# quadrature_generator.net
KiCad netlist of a schematic drawn in EAGLE
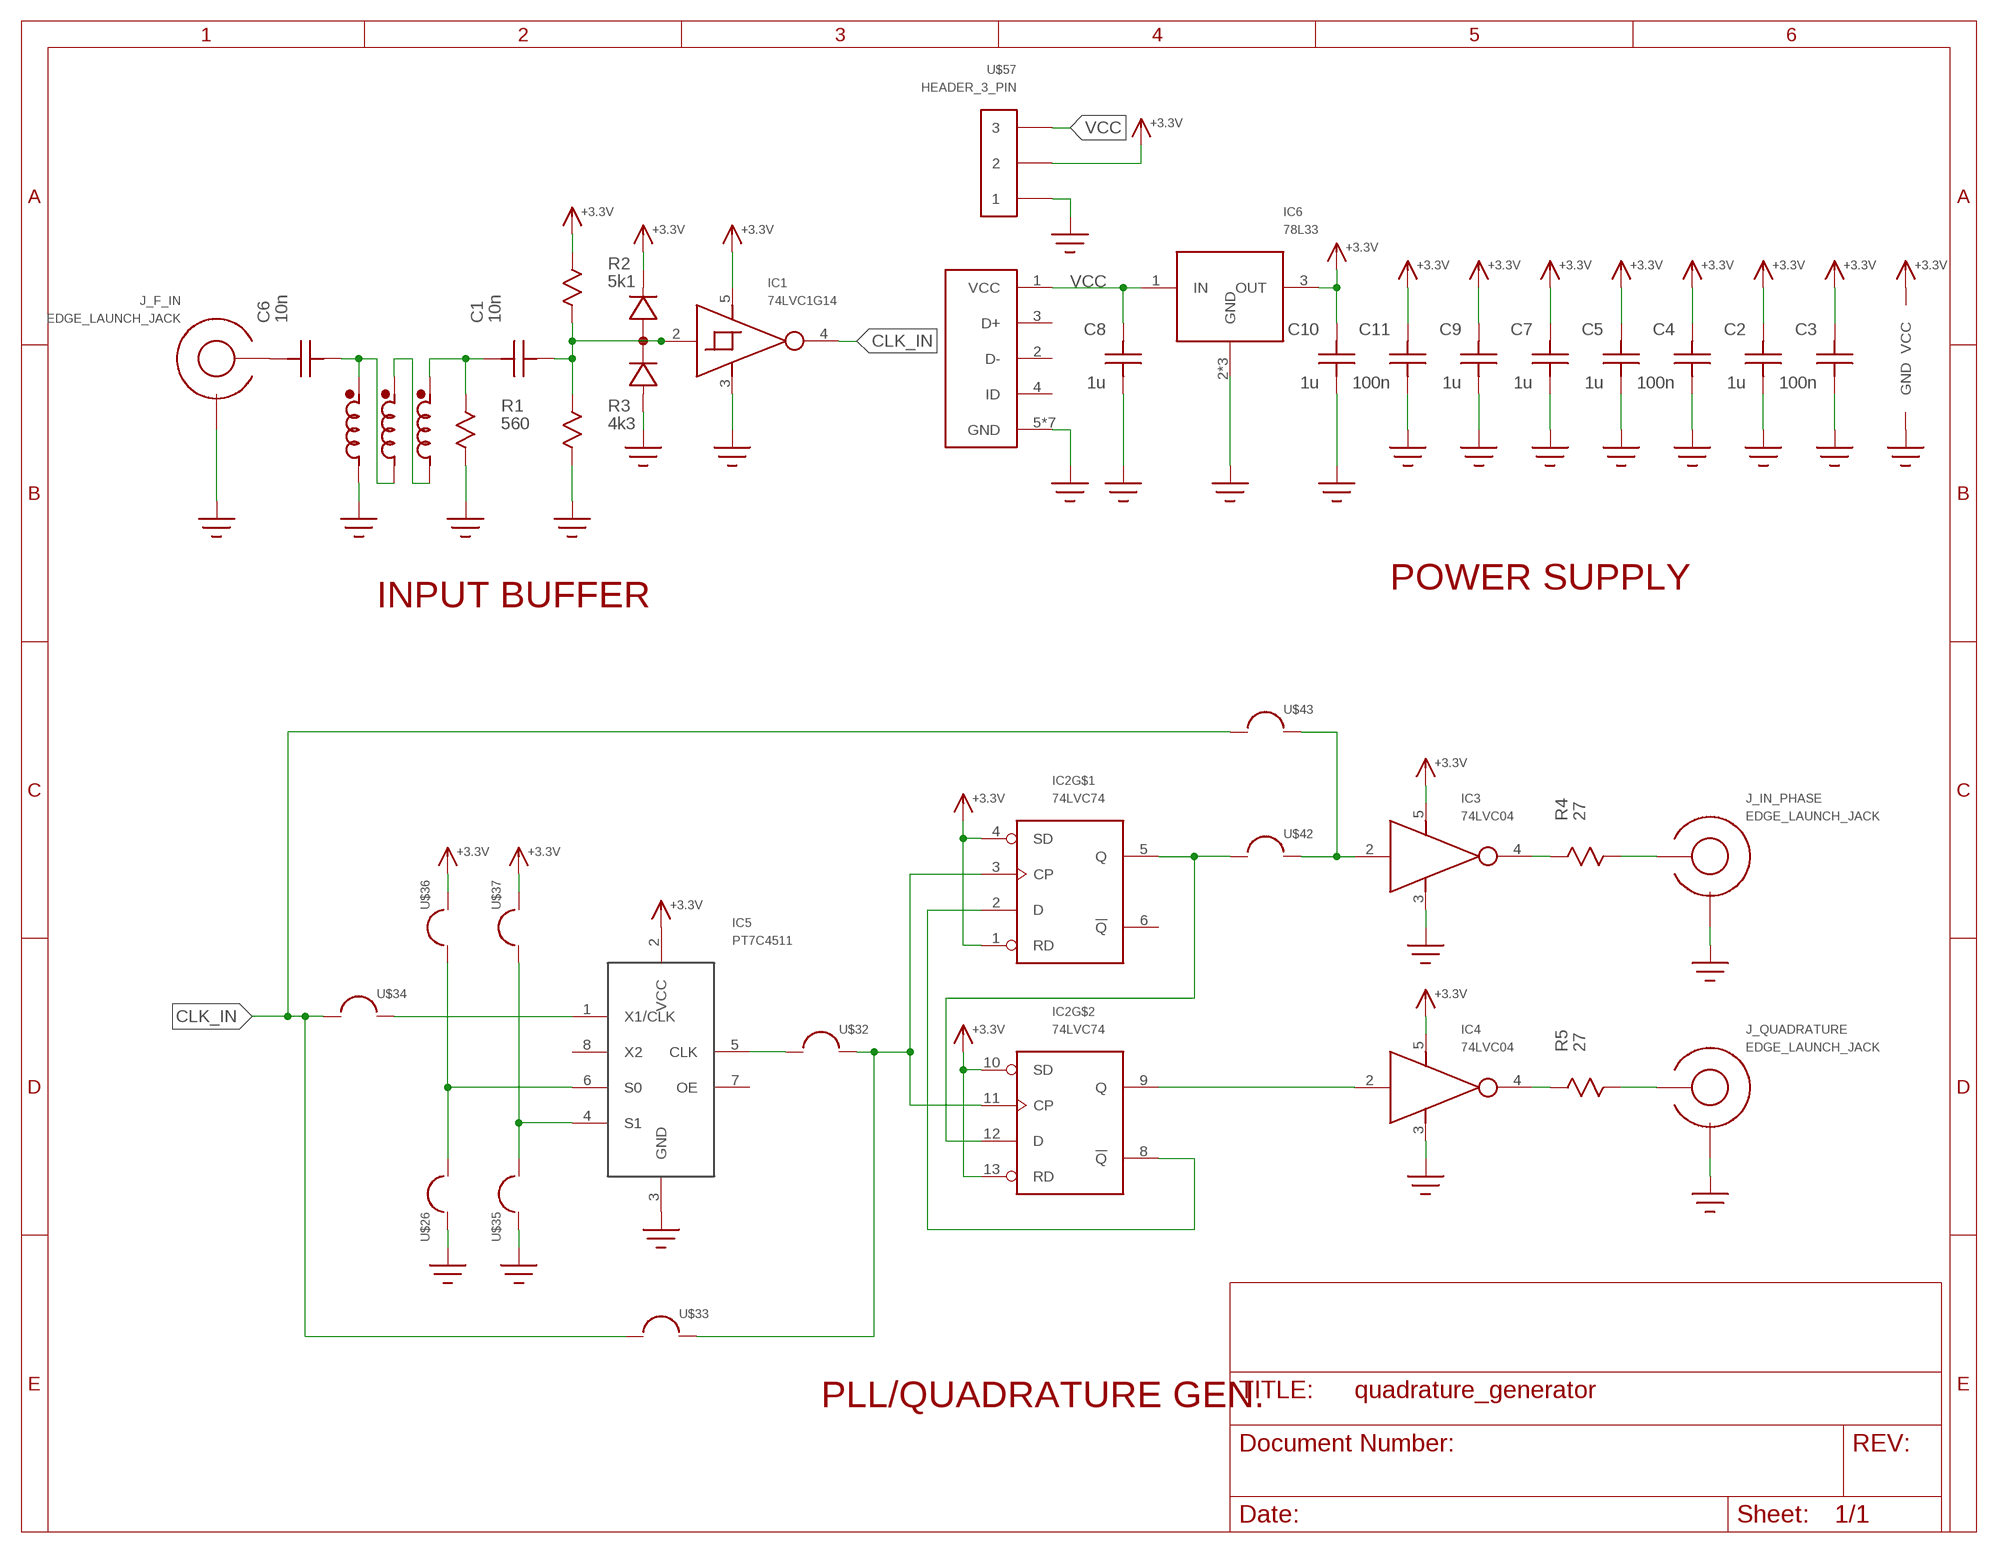
[diagram p0: schematic, sheet 1]

(export (version "E")
  (design (tool "Eeschema 10.0.6"))
  (components
    (comp (ref "C1")
      (value "10n")
      (footprint "eagle-import:0805")
      (libsource (lib "eagle-import") (part "C0805"))
    )
    (comp (ref "C2")
      (value "1u")
      (footprint "eagle-import:0805")
      (libsource (lib "eagle-import") (part "C0805"))
    )
    (comp (ref "C3")
      (value "100n")
      (footprint "eagle-import:0805")
      (libsource (lib "eagle-import") (part "C0805"))
    )
    (comp (ref "C4")
      (value "100n")
      (footprint "eagle-import:0805")
      (libsource (lib "eagle-import") (part "C0805"))
    )
    (comp (ref "C5")
      (value "1u")
      (footprint "eagle-import:0805")
      (libsource (lib "eagle-import") (part "C0805"))
    )
    (comp (ref "C6")
      (value "10n")
      (footprint "eagle-import:0805")
      (libsource (lib "eagle-import") (part "C0805"))
    )
    (comp (ref "C7")
      (value "1u")
      (footprint "eagle-import:0805")
      (libsource (lib "eagle-import") (part "C0805"))
    )
    (comp (ref "C8")
      (value "1u")
      (footprint "eagle-import:0805")
      (libsource (lib "eagle-import") (part "C0805"))
    )
    (comp (ref "C9")
      (value "1u")
      (footprint "eagle-import:0805")
      (libsource (lib "eagle-import") (part "C0805"))
    )
    (comp (ref "C10")
      (value "1u")
      (footprint "eagle-import:0805")
      (libsource (lib "eagle-import") (part "C0805"))
    )
    (comp (ref "C11")
      (value "100n")
      (footprint "eagle-import:0805")
      (libsource (lib "eagle-import") (part "C0805"))
    )
    (comp (ref "IC1")
      (value "74LVC1G14")
      (footprint "eagle-import:SOT23-5")
      (libsource (lib "eagle-import") (part "74LVC1G14"))
    )
    (comp (ref "IC2")
      (value "74LVC74")
      (footprint "eagle-import:SOIC14_NARROW")
      (libsource (lib "eagle-import") (part "74LVC74"))
    )
    (comp (ref "IC3")
      (value "74LVC04")
      (footprint "eagle-import:SOT23-5")
      (libsource (lib "eagle-import") (part "74LVC04"))
    )
    (comp (ref "IC4")
      (value "74LVC04")
      (footprint "eagle-import:SOT23-5")
      (libsource (lib "eagle-import") (part "74LVC04"))
    )
    (comp (ref "IC5")
      (value "PT7C4511")
      (footprint "eagle-import:SOIC8")
      (libsource (lib "eagle-import") (part "PT7C4511"))
    )
    (comp (ref "IC6")
      (value "78L33")
      (footprint "eagle-import:SOT-89")
      (libsource (lib "eagle-import") (part "REGULATOR_3TERM"))
    )
    (comp (ref "J_F_IN")
      (value "EDGE_LAUNCH_JACK")
      (footprint "eagle-import:EDGE_LAUNCH_RF_CON")
      (libsource (lib "eagle-import") (part "EDGE_LAUNCH_JACK"))
    )
    (comp (ref "J_IN_PHASE")
      (value "EDGE_LAUNCH_JACK")
      (footprint "eagle-import:EDGE_LAUNCH_RF_CON")
      (libsource (lib "eagle-import") (part "EDGE_LAUNCH_JACK"))
    )
    (comp (ref "J_QUADRATURE")
      (value "EDGE_LAUNCH_JACK")
      (footprint "eagle-import:EDGE_LAUNCH_RF_CON")
      (libsource (lib "eagle-import") (part "EDGE_LAUNCH_JACK"))
    )
    (comp (ref "R1")
      (value "560")
      (footprint "eagle-import:R1206")
      (libsource (lib "eagle-import") (part "R1206"))
    )
    (comp (ref "R2")
      (value "5k1")
      (footprint "eagle-import:R0805")
      (libsource (lib "eagle-import") (part "R0805"))
    )
    (comp (ref "R3")
      (value "4k3")
      (footprint "eagle-import:R0805")
      (libsource (lib "eagle-import") (part "R0805"))
    )
    (comp (ref "R4")
      (value "27")
      (footprint "eagle-import:R1206")
      (libsource (lib "eagle-import") (part "R1206"))
    )
    (comp (ref "R5")
      (value "27")
      (footprint "eagle-import:R1206")
      (libsource (lib "eagle-import") (part "R1206"))
    )
    (comp (ref "U$1")
      (value "FT37_TRIFILAR_1")
      (footprint "eagle-import:FT37_TRIFILAR_VERT_NC")
      (libsource (lib "eagle-import") (part "FT37_TRIFILAR_1"))
    )
    (comp (ref "U$18")
      (value "USB_JACK")
      (footprint "eagle-import:FCI_MICRO_USB")
      (libsource (lib "eagle-import") (part "USB_JACK"))
    )
    (comp (ref "U$26")
      (value "SOLDER_BRIDGE")
      (footprint "eagle-import:SOLDER_BRIDGE")
      (libsource (lib "eagle-import") (part "SOLDER_BRIDGE"))
    )
    (comp (ref "U$32")
      (value "SOLDER_BRIDGE")
      (footprint "eagle-import:SOLDER_BRIDGE")
      (libsource (lib "eagle-import") (part "SOLDER_BRIDGE"))
    )
    (comp (ref "U$33")
      (value "SOLDER_BRIDGE")
      (footprint "eagle-import:SOLDER_BRIDGE")
      (libsource (lib "eagle-import") (part "SOLDER_BRIDGE"))
    )
    (comp (ref "U$34")
      (value "SOLDER_BRIDGE")
      (footprint "eagle-import:SOLDER_BRIDGE")
      (libsource (lib "eagle-import") (part "SOLDER_BRIDGE"))
    )
    (comp (ref "U$35")
      (value "SOLDER_BRIDGE")
      (footprint "eagle-import:SOLDER_BRIDGE")
      (libsource (lib "eagle-import") (part "SOLDER_BRIDGE"))
    )
    (comp (ref "U$36")
      (value "SOLDER_BRIDGE")
      (footprint "eagle-import:SOLDER_BRIDGE")
      (libsource (lib "eagle-import") (part "SOLDER_BRIDGE"))
    )
    (comp (ref "U$37")
      (value "SOLDER_BRIDGE")
      (footprint "eagle-import:SOLDER_BRIDGE")
      (libsource (lib "eagle-import") (part "SOLDER_BRIDGE"))
    )
    (comp (ref "U$42")
      (value "SOLDER_BRIDGE")
      (footprint "eagle-import:SOLDER_BRIDGE")
      (libsource (lib "eagle-import") (part "SOLDER_BRIDGE"))
    )
    (comp (ref "U$43")
      (value "SOLDER_BRIDGE")
      (footprint "eagle-import:SOLDER_BRIDGE")
      (libsource (lib "eagle-import") (part "SOLDER_BRIDGE"))
    )
    (comp (ref "U$50")
      (value "MMBD7000L")
      (footprint "eagle-import:SOT-23")
      (libsource (lib "eagle-import") (part "MMBD7000L"))
    )
    (comp (ref "U$57")
      (value "HEADER_3_PIN")
      (footprint "eagle-import:HEADER_3_PIN")
      (libsource (lib "eagle-import") (part "HEADER_3_PIN"))
    )
  )
  (nets
    (net (code "1") (name "+3.3V") (class "Default")
      (node (ref "C10") (pin "P$1") (pinfunction "P$1_P$1") (pintype "bidirectional"))
      (node (ref "C11") (pin "P$1") (pinfunction "P$1_P$1") (pintype "bidirectional"))
      (node (ref "C2") (pin "P$1") (pinfunction "P$1_P$1") (pintype "bidirectional"))
      (node (ref "C3") (pin "P$1") (pinfunction "P$1_P$1") (pintype "bidirectional"))
      (node (ref "C4") (pin "P$1") (pinfunction "P$1_P$1") (pintype "bidirectional"))
      (node (ref "C5") (pin "P$1") (pinfunction "P$1_P$1") (pintype "bidirectional"))
      (node (ref "C7") (pin "P$1") (pinfunction "P$1_P$1") (pintype "bidirectional"))
      (node (ref "C9") (pin "P$1") (pinfunction "P$1_P$1") (pintype "bidirectional"))
      (node (ref "IC1") (pin "5") (pinfunction "VCC_5") (pintype "bidirectional"))
      (node (ref "IC2") (pin "1") (pinfunction "RD_1") (pintype "bidirectional"))
      (node (ref "IC2") (pin "10") (pinfunction "SD_10") (pintype "bidirectional"))
      (node (ref "IC2") (pin "13") (pinfunction "RD_13") (pintype "bidirectional"))
      (node (ref "IC2") (pin "14") (pinfunction "VCC_14") (pintype "bidirectional"))
      (node (ref "IC2") (pin "4") (pinfunction "SD_4") (pintype "bidirectional"))
      (node (ref "IC3") (pin "5") (pinfunction "VCC_5") (pintype "bidirectional"))
      (node (ref "IC4") (pin "5") (pinfunction "VCC_5") (pintype "bidirectional"))
      (node (ref "IC5") (pin "2") (pinfunction "VCC_2") (pintype "bidirectional"))
      (node (ref "IC6") (pin "3") (pinfunction "OUT_3") (pintype "bidirectional"))
      (node (ref "R2") (pin "P$1") (pinfunction "P$3_P$1") (pintype "bidirectional"))
      (node (ref "U$36") (pin "2@1") (pinfunction "P$2_2@1") (pintype "bidirectional"))
      (node (ref "U$36") (pin "2@2") (pinfunction "P$2_2@2") (pintype "bidirectional"))
      (node (ref "U$36") (pin "2@3") (pinfunction "P$2_2@3") (pintype "bidirectional"))
      (node (ref "U$37") (pin "2@1") (pinfunction "P$2_2@1") (pintype "bidirectional"))
      (node (ref "U$37") (pin "2@2") (pinfunction "P$2_2@2") (pintype "bidirectional"))
      (node (ref "U$37") (pin "2@3") (pinfunction "P$2_2@3") (pintype "bidirectional"))
      (node (ref "U$50") (pin "2") (pinfunction "CATHODE_2") (pintype "bidirectional"))
      (node (ref "U$57") (pin "2") (pinfunction "2_2") (pintype "bidirectional"))
    )
    (net (code "2") (name "CLK_IN") (class "Default")
      (node (ref "IC1") (pin "4") (pinfunction "OUT_4") (pintype "bidirectional"))
      (node (ref "U$33") (pin "1") (pinfunction "P$1_1") (pintype "bidirectional"))
      (node (ref "U$34") (pin "1") (pinfunction "P$1_1") (pintype "bidirectional"))
      (node (ref "U$43") (pin "1") (pinfunction "P$1_1") (pintype "bidirectional"))
    )
    (net (code "3") (name "GND") (class "Default")
      (node (ref "C10") (pin "P$2") (pinfunction "P$2_P$2") (pintype "bidirectional"))
      (node (ref "C11") (pin "P$2") (pinfunction "P$2_P$2") (pintype "bidirectional"))
      (node (ref "C2") (pin "P$2") (pinfunction "P$2_P$2") (pintype "bidirectional"))
      (node (ref "C3") (pin "P$2") (pinfunction "P$2_P$2") (pintype "bidirectional"))
      (node (ref "C4") (pin "P$2") (pinfunction "P$2_P$2") (pintype "bidirectional"))
      (node (ref "C5") (pin "P$2") (pinfunction "P$2_P$2") (pintype "bidirectional"))
      (node (ref "C7") (pin "P$2") (pinfunction "P$2_P$2") (pintype "bidirectional"))
      (node (ref "C8") (pin "P$2") (pinfunction "P$2_P$2") (pintype "bidirectional"))
      (node (ref "C9") (pin "P$2") (pinfunction "P$2_P$2") (pintype "bidirectional"))
      (node (ref "IC1") (pin "3") (pinfunction "GND_3") (pintype "bidirectional"))
      (node (ref "IC2") (pin "7") (pinfunction "GND_7") (pintype "bidirectional"))
      (node (ref "IC3") (pin "3") (pinfunction "GND_3") (pintype "bidirectional"))
      (node (ref "IC4") (pin "3") (pinfunction "GND_3") (pintype "bidirectional"))
      (node (ref "IC5") (pin "3") (pinfunction "GND_3") (pintype "bidirectional"))
      (node (ref "IC6") (pin "2") (pinfunction "GND_2") (pintype "bidirectional"))
      (node (ref "IC6") (pin "TAB") (pinfunction "GND_TAB") (pintype "bidirectional"))
      (node (ref "IC6") (pin "TAB@1") (pinfunction "GND_TAB@1") (pintype "bidirectional"))
      (node (ref "J_F_IN") (pin "GND@1") (pinfunction "GND_GND@1") (pintype "bidirectional"))
      (node (ref "J_F_IN") (pin "GND@2") (pinfunction "GND_GND@2") (pintype "bidirectional"))
      (node (ref "J_IN_PHASE") (pin "GND@1") (pinfunction "GND_GND@1") (pintype "bidirectional"))
      (node (ref "J_IN_PHASE") (pin "GND@2") (pinfunction "GND_GND@2") (pintype "bidirectional"))
      (node (ref "J_QUADRATURE") (pin "GND@1") (pinfunction "GND_GND@1") (pintype "bidirectional"))
      (node (ref "J_QUADRATURE") (pin "GND@2") (pinfunction "GND_GND@2") (pintype "bidirectional"))
      (node (ref "R1") (pin "P$2") (pinfunction "P$4_P$2") (pintype "bidirectional"))
      (node (ref "R3") (pin "P$2") (pinfunction "P$4_P$2") (pintype "bidirectional"))
      (node (ref "U$1") (pin "P$R1") (pinfunction "R1_P$R1") (pintype "bidirectional"))
      (node (ref "U$18") (pin "5") (pinfunction "GND_5") (pintype "bidirectional"))
      (node (ref "U$18") (pin "GND1") (pinfunction "GND_GND1") (pintype "bidirectional"))
      (node (ref "U$18") (pin "GND2") (pinfunction "GND_GND2") (pintype "bidirectional"))
      (node (ref "U$18") (pin "GND3") (pinfunction "GND_GND3") (pintype "bidirectional"))
      (node (ref "U$18") (pin "GND4") (pinfunction "GND_GND4") (pintype "bidirectional"))
      (node (ref "U$18") (pin "GND5") (pinfunction "GND_GND5") (pintype "bidirectional"))
      (node (ref "U$18") (pin "GND6") (pinfunction "GND_GND6") (pintype "bidirectional"))
      (node (ref "U$26") (pin "2@1") (pinfunction "P$2_2@1") (pintype "bidirectional"))
      (node (ref "U$26") (pin "2@2") (pinfunction "P$2_2@2") (pintype "bidirectional"))
      (node (ref "U$26") (pin "2@3") (pinfunction "P$2_2@3") (pintype "bidirectional"))
      (node (ref "U$35") (pin "2@1") (pinfunction "P$2_2@1") (pintype "bidirectional"))
      (node (ref "U$35") (pin "2@2") (pinfunction "P$2_2@2") (pintype "bidirectional"))
      (node (ref "U$35") (pin "2@3") (pinfunction "P$2_2@3") (pintype "bidirectional"))
      (node (ref "U$50") (pin "1") (pinfunction "ANODE_1") (pintype "bidirectional"))
      (node (ref "U$57") (pin "1") (pinfunction "1_1") (pintype "bidirectional"))
    )
    (net (code "4") (name "Net-(C6-PadP$2)") (class "Default")
      (node (ref "C6") (pin "P$2") (pinfunction "P$2_P$2") (pintype "bidirectional"))
      (node (ref "J_F_IN") (pin "SIG") (pinfunction "SIG_SIG") (pintype "bidirectional"))
    )
    (net (code "5") (name "Net-(IC1-IN)") (class "Default")
      (node (ref "C1") (pin "P$1") (pinfunction "P$1_P$1") (pintype "bidirectional"))
      (node (ref "IC1") (pin "2") (pinfunction "IN_2") (pintype "bidirectional"))
      (node (ref "R2") (pin "P$2") (pinfunction "P$4_P$2") (pintype "bidirectional"))
      (node (ref "R3") (pin "P$1") (pinfunction "P$3_P$1") (pintype "bidirectional"))
      (node (ref "U$50") (pin "3") (pinfunction "COMMON_3") (pintype "bidirectional"))
    )
    (net (code "6") (name "Net-(IC2A-CP)") (class "Default")
      (node (ref "IC2") (pin "11") (pinfunction "CP_11") (pintype "bidirectional"))
      (node (ref "IC2") (pin "3") (pinfunction "CP_3") (pintype "bidirectional"))
      (node (ref "U$32") (pin "2@1") (pinfunction "P$2_2@1") (pintype "bidirectional"))
      (node (ref "U$32") (pin "2@2") (pinfunction "P$2_2@2") (pintype "bidirectional"))
      (node (ref "U$32") (pin "2@3") (pinfunction "P$2_2@3") (pintype "bidirectional"))
      (node (ref "U$33") (pin "2@1") (pinfunction "P$2_2@1") (pintype "bidirectional"))
      (node (ref "U$33") (pin "2@2") (pinfunction "P$2_2@2") (pintype "bidirectional"))
      (node (ref "U$33") (pin "2@3") (pinfunction "P$2_2@3") (pintype "bidirectional"))
    )
    (net (code "7") (name "Net-(IC2A-D)") (class "Default")
      (node (ref "IC2") (pin "2") (pinfunction "D_2") (pintype "bidirectional"))
      (node (ref "IC2") (pin "8") (pinfunction "~{Q}_8") (pintype "bidirectional"))
    )
    (net (code "8") (name "Net-(IC2A-Q)") (class "Default")
      (node (ref "IC2") (pin "12") (pinfunction "D_12") (pintype "bidirectional"))
      (node (ref "IC2") (pin "5") (pinfunction "Q_5") (pintype "bidirectional"))
      (node (ref "U$42") (pin "1") (pinfunction "P$1_1") (pintype "bidirectional"))
    )
    (net (code "9") (name "Net-(IC2B-Q)") (class "Default")
      (node (ref "IC2") (pin "9") (pinfunction "Q_9") (pintype "bidirectional"))
      (node (ref "IC4") (pin "2") (pinfunction "IN_2") (pintype "bidirectional"))
    )
    (net (code "10") (name "Net-(IC3-IN)") (class "Default")
      (node (ref "IC3") (pin "2") (pinfunction "IN_2") (pintype "bidirectional"))
      (node (ref "U$42") (pin "2@1") (pinfunction "P$2_2@1") (pintype "bidirectional"))
      (node (ref "U$42") (pin "2@2") (pinfunction "P$2_2@2") (pintype "bidirectional"))
      (node (ref "U$42") (pin "2@3") (pinfunction "P$2_2@3") (pintype "bidirectional"))
      (node (ref "U$43") (pin "2@1") (pinfunction "P$2_2@1") (pintype "bidirectional"))
      (node (ref "U$43") (pin "2@2") (pinfunction "P$2_2@2") (pintype "bidirectional"))
      (node (ref "U$43") (pin "2@3") (pinfunction "P$2_2@3") (pintype "bidirectional"))
    )
    (net (code "11") (name "Net-(IC3-OUT)") (class "Default")
      (node (ref "IC3") (pin "4") (pinfunction "OUT_4") (pintype "bidirectional"))
      (node (ref "R4") (pin "P$1") (pinfunction "P$3_P$1") (pintype "bidirectional"))
    )
    (net (code "12") (name "Net-(IC4-OUT)") (class "Default")
      (node (ref "IC4") (pin "4") (pinfunction "OUT_4") (pintype "bidirectional"))
      (node (ref "R5") (pin "P$1") (pinfunction "P$3_P$1") (pintype "bidirectional"))
    )
    (net (code "13") (name "Net-(IC5-CLK)") (class "Default")
      (node (ref "IC5") (pin "5") (pinfunction "CLK_5") (pintype "bidirectional"))
      (node (ref "U$32") (pin "1") (pinfunction "P$1_1") (pintype "bidirectional"))
    )
    (net (code "14") (name "Net-(IC5-S0)") (class "Default")
      (node (ref "IC5") (pin "6") (pinfunction "S0_6") (pintype "bidirectional"))
      (node (ref "U$26") (pin "1") (pinfunction "P$1_1") (pintype "bidirectional"))
      (node (ref "U$36") (pin "1") (pinfunction "P$1_1") (pintype "bidirectional"))
    )
    (net (code "15") (name "Net-(IC5-S1)") (class "Default")
      (node (ref "IC5") (pin "4") (pinfunction "S1_4") (pintype "bidirectional"))
      (node (ref "U$35") (pin "1") (pinfunction "P$1_1") (pintype "bidirectional"))
      (node (ref "U$37") (pin "1") (pinfunction "P$1_1") (pintype "bidirectional"))
    )
    (net (code "16") (name "Net-(IC5-X1{slash}CLK)") (class "Default")
      (node (ref "IC5") (pin "1") (pinfunction "X1/CLK_1") (pintype "bidirectional"))
      (node (ref "U$34") (pin "2@1") (pinfunction "P$2_2@1") (pintype "bidirectional"))
      (node (ref "U$34") (pin "2@2") (pinfunction "P$2_2@2") (pintype "bidirectional"))
      (node (ref "U$34") (pin "2@3") (pinfunction "P$2_2@3") (pintype "bidirectional"))
    )
    (net (code "17") (name "Net-(R1-P$3)") (class "Default")
      (node (ref "C1") (pin "P$2") (pinfunction "P$2_P$2") (pintype "bidirectional"))
      (node (ref "R1") (pin "P$1") (pinfunction "P$3_P$1") (pintype "bidirectional"))
      (node (ref "U$1") (pin "P$Y2") (pinfunction "Y2_P$Y2") (pintype "bidirectional"))
    )
    (net (code "18") (name "Net-(R4-P$4)") (class "Default")
      (node (ref "J_IN_PHASE") (pin "SIG") (pinfunction "SIG_SIG") (pintype "bidirectional"))
      (node (ref "R4") (pin "P$2") (pinfunction "P$4_P$2") (pintype "bidirectional"))
    )
    (net (code "19") (name "Net-(R5-P$4)") (class "Default")
      (node (ref "J_QUADRATURE") (pin "SIG") (pinfunction "SIG_SIG") (pintype "bidirectional"))
      (node (ref "R5") (pin "P$2") (pinfunction "P$4_P$2") (pintype "bidirectional"))
    )
    (net (code "20") (name "Net-(U$1-G1)") (class "Default")
      (node (ref "C6") (pin "P$1") (pinfunction "P$1_P$1") (pintype "bidirectional"))
      (node (ref "U$1") (pin "P$G1") (pinfunction "G1_P$G1") (pintype "bidirectional"))
      (node (ref "U$1") (pin "P$R2") (pinfunction "R2_P$R2") (pintype "bidirectional"))
    )
    (net (code "21") (name "Net-(U$1-G2)") (class "Default")
      (node (ref "U$1") (pin "P$G2") (pinfunction "G2_P$G2") (pintype "bidirectional"))
      (node (ref "U$1") (pin "P$Y1") (pinfunction "Y1_P$Y1") (pintype "bidirectional"))
    )
    (net (code "22") (name "VCC") (class "Default")
      (node (ref "C8") (pin "P$1") (pinfunction "P$1_P$1") (pintype "bidirectional"))
      (node (ref "IC6") (pin "1") (pinfunction "IN_1") (pintype "bidirectional"))
      (node (ref "U$18") (pin "1") (pinfunction "VCC_1") (pintype "bidirectional"))
      (node (ref "U$57") (pin "3") (pinfunction "3_3") (pintype "bidirectional"))
    )
    (net (code "23") (name "unconnected-(IC2A-~{Q}-Pad6)") (class "Default")
      (node (ref "IC2") (pin "6") (pinfunction "~{Q}_6") (pintype "bidirectional"))
    )
    (net (code "24") (name "unconnected-(IC5-OE-Pad7)") (class "Default")
      (node (ref "IC5") (pin "7") (pinfunction "OE_7") (pintype "bidirectional"))
    )
    (net (code "25") (name "unconnected-(IC5-X2-Pad8)") (class "Default")
      (node (ref "IC5") (pin "8") (pinfunction "X2_8") (pintype "bidirectional"))
    )
    (net (code "26") (name "unconnected-(U$18-D+-Pad3)") (class "Default")
      (node (ref "U$18") (pin "3") (pinfunction "D+_3") (pintype "bidirectional"))
    )
    (net (code "27") (name "unconnected-(U$18-D--Pad2)") (class "Default")
      (node (ref "U$18") (pin "2") (pinfunction "D-_2") (pintype "bidirectional"))
    )
    (net (code "28") (name "unconnected-(U$18-ID-Pad4)") (class "Default")
      (node (ref "U$18") (pin "4") (pinfunction "ID_4") (pintype "bidirectional"))
    )
  )
)
